# Tracking-Car.net
KiCad netlist of a schematic drawn in Altium Designer
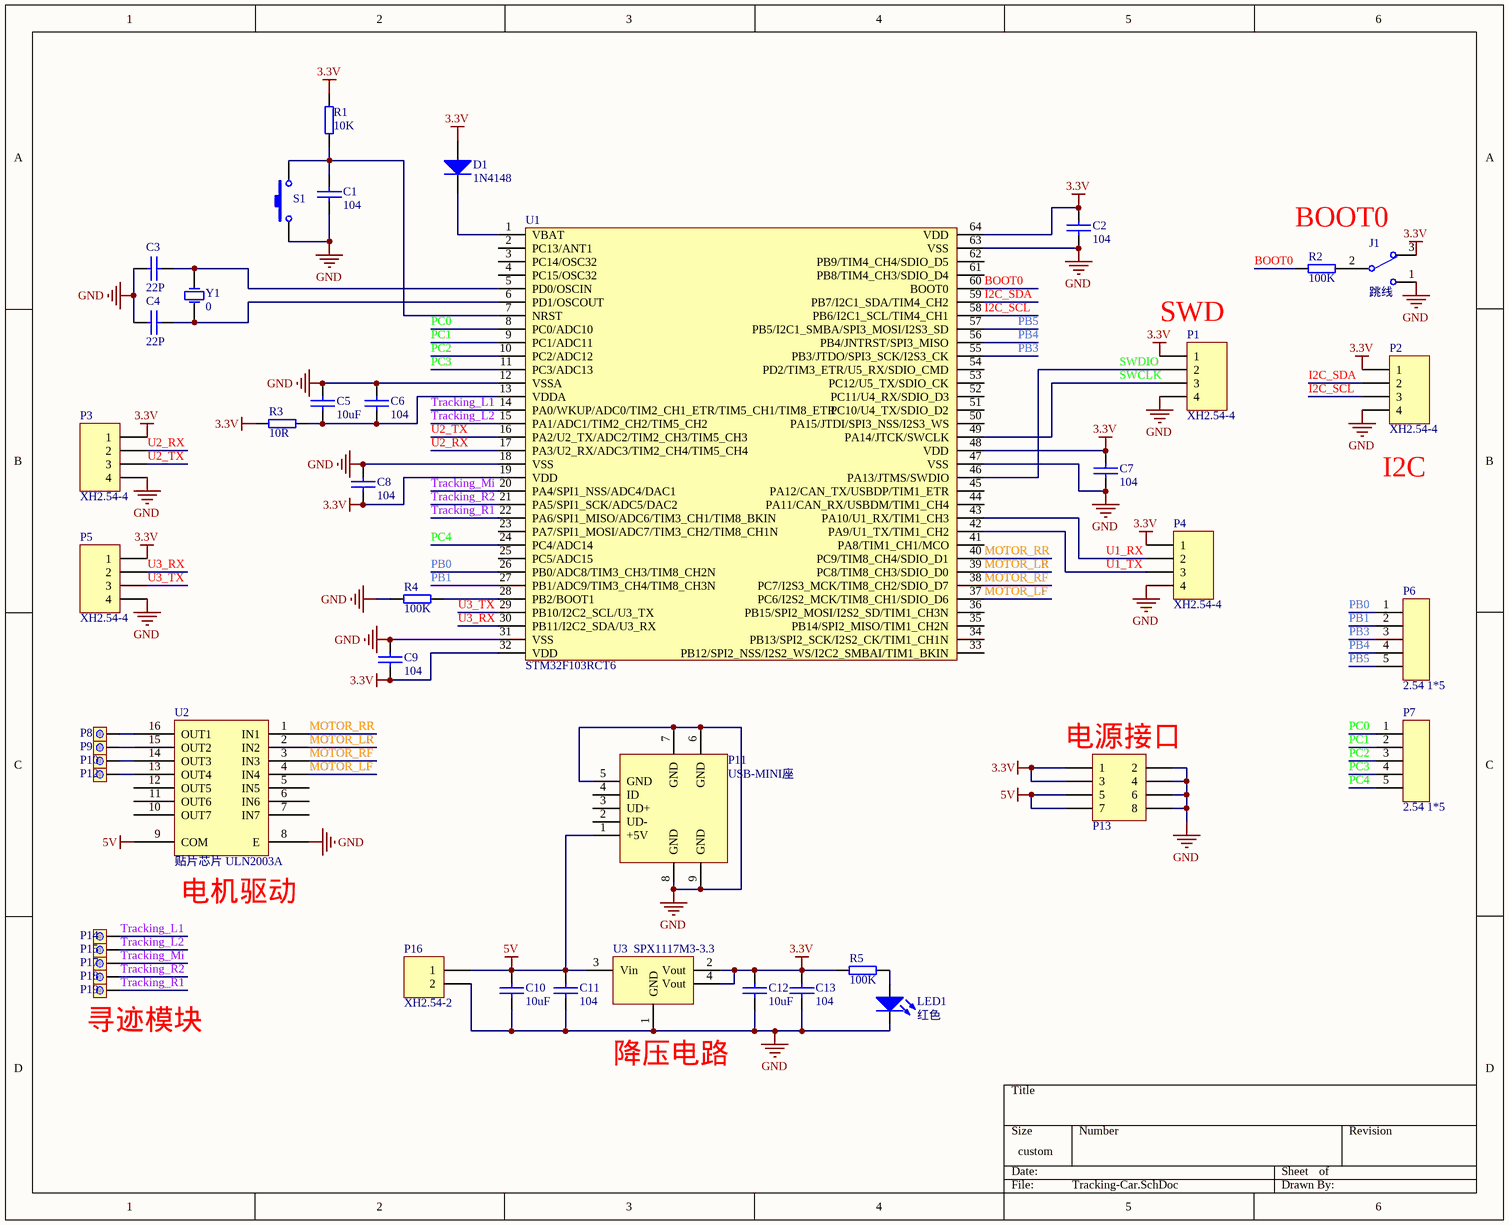
[diagram p0: Tracking-Car.SchDoc]

(export (version "E")
  (design (tool "Eeschema 10.0.6"))
  (components
    (comp (ref "C1")
      (value "104")
      (footprint "0805")
      (libsource (lib "Sch_Device_veryaz") (part "电容 贴片 0805"))
    )
    (comp (ref "C2")
      (value "104")
      (footprint "0805")
      (libsource (lib "Sch_Device_veryaz") (part "电容 贴片 0805"))
    )
    (comp (ref "C3")
      (value "22P")
      (footprint "0805")
      (libsource (lib "Sch_Device_veryaz") (part "电容 贴片 0805"))
    )
    (comp (ref "C4")
      (value "22P")
      (footprint "0805")
      (libsource (lib "Sch_Device_veryaz") (part "电容 贴片 0805"))
    )
    (comp (ref "C5")
      (value "10uF")
      (footprint "0805")
      (libsource (lib "Sch_Device_veryaz") (part "电容 贴片 0805"))
    )
    (comp (ref "C6")
      (value "104")
      (footprint "0805")
      (libsource (lib "Sch_Device_veryaz") (part "电容 贴片 0805"))
    )
    (comp (ref "C7")
      (value "104")
      (footprint "0805")
      (libsource (lib "Sch_Device_veryaz") (part "电容 贴片 0805"))
    )
    (comp (ref "C8")
      (value "104")
      (footprint "0805")
      (libsource (lib "Sch_Device_veryaz") (part "电容 贴片 0805"))
    )
    (comp (ref "C9")
      (value "104")
      (footprint "0805")
      (libsource (lib "Sch_Device_veryaz") (part "电容 贴片 0805"))
    )
    (comp (ref "C10")
      (value "10uF")
      (footprint "0805")
      (libsource (lib "Sch_Device_veryaz") (part "电容 贴片 0805"))
    )
    (comp (ref "C11")
      (value "104")
      (footprint "0805")
      (libsource (lib "Sch_Device_veryaz") (part "电容 贴片 0805"))
    )
    (comp (ref "C12")
      (value "10uF")
      (footprint "0805")
      (libsource (lib "Sch_Device_veryaz") (part "电容 贴片 0805"))
    )
    (comp (ref "C13")
      (value "104")
      (footprint "0805")
      (libsource (lib "Sch_Device_veryaz") (part "电容 贴片 0805"))
    )
    (comp (ref "D1")
      (value "1N4148")
      (footprint "二极管 贴片 IN4148")
      (libsource (lib "Sch_Device_veryaz") (part "二极管 贴片 1N4148"))
    )
    (comp (ref "J1")
      (value "跳线")
      (footprint "单排插针 2.54 1*3")
      (libsource (lib "Sch_Device_veryaz") (part "联结件 跳线端子 2.54-3"))
    )
    (comp (ref "LED1")
      (value "红色")
      (footprint "LED0805")
      (libsource (lib "Sch_Device_veryaz") (part "二极管 贴片发光 0805"))
    )
    (comp (ref "P1")
      (value "XH2.54-4")
      (footprint "VH2.54_4")
      (libsource (lib "Sch_Device_veryaz") (part "联结件 XH2.54-4"))
    )
    (comp (ref "P2")
      (value "XH2.54-4")
      (footprint "VH2.54_4")
      (libsource (lib "Sch_Device_veryaz") (part "联结件 XH2.54-4"))
    )
    (comp (ref "P3") (value "XH2.54-4") (footprint "VH2.54_4") (libsource (lib "") (part "联结件 XH2.54-4_1")))
    (comp (ref "P4")
      (value "XH2.54-4")
      (footprint "VH2.54_4")
      (libsource (lib "Sch_Device_veryaz") (part "联结件 XH2.54-4"))
    )
    (comp (ref "P5") (value "XH2.54-4") (footprint "VH2.54_4") (libsource (lib "") (part "联结件 XH2.54-4_1")))
    (comp (ref "P6")
      (value "2.54 1*5")
      (footprint "单排插针 2.54 1*5")
      (libsource (lib "Sch_Device_veryaz") (part "联结件 单排插针 2.54 1*5"))
    )
    (comp (ref "P7")
      (value "2.54 1*5")
      (footprint "单排插针 2.54 1*5")
      (libsource (lib "Sch_Device_veryaz") (part "联结件 单排插针 2.54 1*5"))
    )
    (comp (ref "P8") (value "TEST") (footprint "焊盘") (libsource (lib "Sch_Device_veryaz") (part "焊盘")))
    (comp (ref "P9") (value "TEST") (footprint "焊盘") (libsource (lib "Sch_Device_veryaz") (part "焊盘")))
    (comp (ref "P10") (value "TEST") (footprint "焊盘") (libsource (lib "Sch_Device_veryaz") (part "焊盘")))
    (comp (ref "P11")
      (value "USB-MINI座")
      (footprint "USB MINI DIP")
      (libsource (lib "Sch_Device_veryaz") (part "联结件 USB-MINI座"))
    )
    (comp (ref "P12") (value "TEST") (footprint "焊盘") (libsource (lib "Sch_Device_veryaz") (part "焊盘")))
    (comp (ref "P13")
      (value "双排插针 2.54 2*4")
      (footprint "双排插针 2.54 2*4")
      (libsource (lib "Sch_Device_veryaz") (part "联结件 双排插针 2.54 2*4"))
    )
    (comp (ref "P14") (value "TEST") (footprint "焊盘") (libsource (lib "Sch_Device_veryaz") (part "焊盘")))
    (comp (ref "P15") (value "TEST") (footprint "焊盘") (libsource (lib "Sch_Device_veryaz") (part "焊盘")))
    (comp (ref "P16")
      (value "XH2.54-2")
      (footprint "VH2.54_2")
      (libsource (lib "Sch_Device_veryaz") (part "联结件 XH2.54-2"))
    )
    (comp (ref "P17") (value "TEST") (footprint "焊盘") (libsource (lib "Sch_Device_veryaz") (part "焊盘")))
    (comp (ref "P18") (value "TEST") (footprint "焊盘") (libsource (lib "Sch_Device_veryaz") (part "焊盘")))
    (comp (ref "P19") (value "TEST") (footprint "焊盘") (libsource (lib "Sch_Device_veryaz") (part "焊盘")))
    (comp (ref "R1") (value "10K") (footprint "0805") (libsource (lib "") (part "电阻 贴片 0805_1")))
    (comp (ref "R2")
      (value "100K")
      (footprint "0805")
      (libsource (lib "Sch_Device_veryaz") (part "电阻 贴片 0805"))
    )
    (comp (ref "R3")
      (value "10R")
      (footprint "0805")
      (libsource (lib "Sch_Device_veryaz") (part "电阻 贴片 0805"))
    )
    (comp (ref "R4")
      (value "100K")
      (footprint "0805")
      (libsource (lib "Sch_Device_veryaz") (part "电阻 贴片 0805"))
    )
    (comp (ref "R5")
      (value "100K")
      (footprint "0805")
      (libsource (lib "Sch_Device_veryaz") (part "电阻 贴片 0805"))
    )
    (comp (ref "S1")
      (value "key")
      (footprint "按键 轻触  6*3")
      (libsource (lib "Sch_Device_veryaz") (part "按键 轻触 3*6"))
    )
    (comp (ref "U1")
      (value "STM32F103RCT6")
      (footprint "Pcb Device_veryaz:LQFP64")
      (description "单片机")
      (libsource (lib "Sch_Device_veryaz") (part "贴片芯片 STM32F103RCT6"))
    )
    (comp (ref "U2")
      (value "贴片芯片 ULN2003A")
      (footprint "SOIC16")
      (libsource (lib "Sch_Device_veryaz") (part "贴片芯片 ULN2003A"))
    )
    (comp (ref "U3")
      (value "SPX1117M3-3.3")
      (footprint "SOT223")
      (description "LDO")
      (libsource (lib "Sch_Device_veryaz") (part "贴片芯片 SPX1117M3-3.3"))
    )
    (comp (ref "Y1")
      (value "0")
      (footprint "晶振 BCY-W2/E4.7")
      (libsource (lib "Sch_Device_veryaz") (part "晶振 直插矮"))
    )
  )
  (nets
    (net (code "1") (name "/BOOT0") (class "Default")
      (node (ref "R2") (pin "2") (pinfunction "2_2") (pintype "passive"))
      (node (ref "U1") (pin "60") (pinfunction "BOOT0_60") (pintype "passive"))
    )
    (net (code "2") (name "/I2C_SCL") (class "Default")
      (node (ref "P2") (pin "3") (pinfunction "3_3") (pintype "passive"))
      (node (ref "U1") (pin "58") (pinfunction "PB6/I2C1_SCL/TIM4_CH1_58") (pintype "passive"))
    )
    (net (code "3") (name "/I2C_SDA") (class "Default")
      (node (ref "P2") (pin "2") (pinfunction "2_2") (pintype "passive"))
      (node (ref "U1") (pin "59") (pinfunction "PB7/I2C1_SDA/TIM4_CH2_59") (pintype "passive"))
    )
    (net (code "4") (name "/MOTOR_LF") (class "Default")
      (node (ref "U1") (pin "37") (pinfunction "PC6/I2S2_MCK/TIM8_CH1/SDIO_D6_37") (pintype "passive"))
      (node (ref "U2") (pin "4") (pinfunction "IN4_4") (pintype "passive"))
    )
    (net (code "5") (name "/MOTOR_LR") (class "Default")
      (node (ref "U1") (pin "39") (pinfunction "PC8/TIM8_CH3/SDIO_D0_39") (pintype "passive"))
      (node (ref "U2") (pin "2") (pinfunction "IN2_2") (pintype "passive"))
    )
    (net (code "6") (name "/MOTOR_RF") (class "Default")
      (node (ref "U1") (pin "38") (pinfunction "PC7/I2S3_MCK/TIM8_CH2/SDIO_D7_38") (pintype "passive"))
      (node (ref "U2") (pin "3") (pinfunction "IN3_3") (pintype "passive"))
    )
    (net (code "7") (name "/MOTOR_RR") (class "Default")
      (node (ref "U1") (pin "40") (pinfunction "PC9/TIM8_CH4/SDIO_D1_40") (pintype "passive"))
      (node (ref "U2") (pin "1") (pinfunction "IN1_1") (pintype "passive"))
    )
    (net (code "8") (name "/PB0") (class "Default")
      (node (ref "P6") (pin "1") (pinfunction "1_1") (pintype "passive"))
      (node (ref "U1") (pin "26") (pinfunction "PB0/ADC8/TIM3_CH3/TIM8_CH2N_26") (pintype "passive"))
    )
    (net (code "9") (name "/PB1") (class "Default")
      (node (ref "P6") (pin "2") (pinfunction "2_2") (pintype "passive"))
      (node (ref "U1") (pin "27") (pinfunction "PB1/ADC9/TIM3_CH4/TIM8_CH3N_27") (pintype "passive"))
    )
    (net (code "10") (name "/PB3") (class "Default")
      (node (ref "P6") (pin "3") (pinfunction "3_3") (pintype "passive"))
      (node (ref "U1") (pin "55") (pinfunction "PB3/JTDO/SPI3_SCK/I2S3_CK_55") (pintype "passive"))
    )
    (net (code "11") (name "/PB4") (class "Default")
      (node (ref "P6") (pin "4") (pinfunction "4_4") (pintype "passive"))
      (node (ref "U1") (pin "56") (pinfunction "PB4/JNTRST/SPI3_MISO_56") (pintype "passive"))
    )
    (net (code "12") (name "/PB5") (class "Default")
      (node (ref "P6") (pin "5") (pinfunction "5_5") (pintype "passive"))
      (node (ref "U1") (pin "57") (pinfunction "PB5/I2C1_SMBA/SPI3_MOSI/I2S3_SD_57") (pintype "passive"))
    )
    (net (code "13") (name "/PC0") (class "Default")
      (node (ref "P7") (pin "1") (pinfunction "1_1") (pintype "passive"))
      (node (ref "U1") (pin "8") (pinfunction "PC0/ADC10_8") (pintype "passive"))
    )
    (net (code "14") (name "/PC1") (class "Default")
      (node (ref "P7") (pin "2") (pinfunction "2_2") (pintype "passive"))
      (node (ref "U1") (pin "9") (pinfunction "PC1/ADC11_9") (pintype "passive"))
    )
    (net (code "15") (name "/PC2") (class "Default")
      (node (ref "P7") (pin "3") (pinfunction "3_3") (pintype "passive"))
      (node (ref "U1") (pin "10") (pinfunction "PC2/ADC12_10") (pintype "passive"))
    )
    (net (code "16") (name "/PC3") (class "Default")
      (node (ref "P7") (pin "4") (pinfunction "4_4") (pintype "passive"))
      (node (ref "U1") (pin "11") (pinfunction "PC3/ADC13_11") (pintype "passive"))
    )
    (net (code "17") (name "/PC4") (class "Default")
      (node (ref "P7") (pin "5") (pinfunction "5_5") (pintype "passive"))
      (node (ref "U1") (pin "24") (pinfunction "PC4/ADC14_24") (pintype "passive"))
    )
    (net (code "18") (name "/SWCLK") (class "Default")
      (node (ref "P1") (pin "3") (pinfunction "3_3") (pintype "passive"))
      (node (ref "U1") (pin "49") (pinfunction "PA14/JTCK/SWCLK_49") (pintype "passive"))
    )
    (net (code "19") (name "/SWDIO") (class "Default")
      (node (ref "P1") (pin "2") (pinfunction "2_2") (pintype "passive"))
      (node (ref "U1") (pin "46") (pinfunction "PA13/JTMS/SWDIO_46") (pintype "passive"))
    )
    (net (code "20") (name "/Tracking_L1") (class "Default")
      (node (ref "P14") (pin "1") (pinfunction "1_1") (pintype "passive"))
      (node (ref "U1") (pin "14") (pinfunction "PA0/WKUP/ADC0/TIM2_CH1_ETR/TIM5_CH1/TIM8_ETR_14") (pintype "passive"))
    )
    (net (code "21") (name "/Tracking_L2") (class "Default")
      (node (ref "P15") (pin "1") (pinfunction "1_1") (pintype "passive"))
      (node (ref "U1") (pin "15") (pinfunction "PA1/ADC1/TIM2_CH2/TIM5_CH2_15") (pintype "passive"))
    )
    (net (code "22") (name "/Tracking_Mi") (class "Default")
      (node (ref "P17") (pin "1") (pinfunction "1_1") (pintype "passive"))
      (node (ref "U1") (pin "20") (pinfunction "PA4/SPI1_NSS/ADC4/DAC1_20") (pintype "passive"))
    )
    (net (code "23") (name "/Tracking_R1") (class "Default")
      (node (ref "P19") (pin "1") (pinfunction "1_1") (pintype "passive"))
      (node (ref "U1") (pin "22") (pinfunction "PA6/SPI1_MISO/ADC6/TIM3_CH1/TIM8_BKIN_22") (pintype "passive"))
    )
    (net (code "24") (name "/Tracking_R2") (class "Default")
      (node (ref "P18") (pin "1") (pinfunction "1_1") (pintype "passive"))
      (node (ref "U1") (pin "21") (pinfunction "PA5/SPI1_SCK/ADC5/DAC2_21") (pintype "passive"))
    )
    (net (code "25") (name "/U1_RX") (class "Default")
      (node (ref "P4") (pin "2") (pinfunction "2_2") (pintype "passive"))
      (node (ref "U1") (pin "43") (pinfunction "PA10/U1_RX/TIM1_CH3_43") (pintype "passive"))
    )
    (net (code "26") (name "/U1_TX") (class "Default")
      (node (ref "P4") (pin "3") (pinfunction "3_3") (pintype "passive"))
      (node (ref "U1") (pin "42") (pinfunction "PA9/U1_TX/TIM1_CH2_42") (pintype "passive"))
    )
    (net (code "27") (name "/U2_RX") (class "Default")
      (node (ref "P3") (pin "2") (pinfunction "2_2") (pintype "passive"))
      (node (ref "U1") (pin "17") (pinfunction "PA3/U2_RX/ADC3/TIM2_CH4/TIM5_CH4_17") (pintype "passive"))
    )
    (net (code "28") (name "/U2_TX") (class "Default")
      (node (ref "P3") (pin "3") (pinfunction "3_3") (pintype "passive"))
      (node (ref "U1") (pin "16") (pinfunction "PA2/U2_TX/ADC2/TIM2_CH3/TIM5_CH3_16") (pintype "passive"))
    )
    (net (code "29") (name "/U3_RX") (class "Default")
      (node (ref "P5") (pin "2") (pinfunction "2_2") (pintype "passive"))
      (node (ref "U1") (pin "30") (pinfunction "PB11/I2C2_SDA/U3_RX_30") (pintype "passive"))
    )
    (net (code "30") (name "/U3_TX") (class "Default")
      (node (ref "P5") (pin "3") (pinfunction "3_3") (pintype "passive"))
      (node (ref "U1") (pin "29") (pinfunction "PB10/I2C2_SCL/U3_TX_29") (pintype "passive"))
    )
    (net (code "31") (name "3.3V") (class "Default")
      (node (ref "C12") (pin "2") (pintype "passive"))
      (node (ref "C13") (pin "2") (pintype "passive"))
      (node (ref "C2") (pin "2") (pintype "passive"))
      (node (ref "C7") (pin "1") (pintype "passive"))
      (node (ref "C8") (pin "1") (pintype "passive"))
      (node (ref "C9") (pin "1") (pintype "passive"))
      (node (ref "D1") (pin "1") (pinfunction "A_1") (pintype "passive"))
      (node (ref "J1") (pin "3") (pinfunction "3_3") (pintype "passive"))
      (node (ref "P1") (pin "1") (pinfunction "1_1") (pintype "passive"))
      (node (ref "P13") (pin "1") (pinfunction "1_1") (pintype "passive"))
      (node (ref "P13") (pin "3") (pinfunction "3_3") (pintype "passive"))
      (node (ref "P2") (pin "1") (pinfunction "1_1") (pintype "passive"))
      (node (ref "P3") (pin "1") (pinfunction "1_1") (pintype "passive"))
      (node (ref "P4") (pin "1") (pinfunction "1_1") (pintype "passive"))
      (node (ref "P5") (pin "1") (pinfunction "1_1") (pintype "passive"))
      (node (ref "R1") (pin "1") (pinfunction "1_1") (pintype "passive"))
      (node (ref "R3") (pin "2") (pinfunction "2_2") (pintype "passive"))
      (node (ref "R5") (pin "2") (pinfunction "2_2") (pintype "passive"))
      (node (ref "U1") (pin "19") (pinfunction "VDD_19") (pintype "passive"))
      (node (ref "U1") (pin "32") (pinfunction "VDD_32") (pintype "passive"))
      (node (ref "U1") (pin "48") (pinfunction "VDD_48") (pintype "passive"))
      (node (ref "U1") (pin "64") (pinfunction "VDD_64") (pintype "passive"))
      (node (ref "U3") (pin "2") (pinfunction "Vout_2") (pintype "passive"))
      (node (ref "U3") (pin "4") (pinfunction "Vout_4") (pintype "passive"))
    )
    (net (code "32") (name "5V") (class "Default")
      (node (ref "C10") (pin "2") (pintype "passive"))
      (node (ref "C11") (pin "2") (pintype "passive"))
      (node (ref "P11") (pin "1") (pinfunction "+5V_1") (pintype "passive"))
      (node (ref "P13") (pin "5") (pinfunction "5_5") (pintype "passive"))
      (node (ref "P13") (pin "7") (pinfunction "7_7") (pintype "passive"))
      (node (ref "P16") (pin "1") (pinfunction "1_1") (pintype "passive"))
      (node (ref "U2") (pin "9") (pinfunction "COM_9") (pintype "passive"))
      (node (ref "U3") (pin "3") (pinfunction "Vin_3") (pintype "passive"))
    )
    (net (code "33") (name "GND") (class "Default")
      (node (ref "C1") (pin "1") (pintype "passive"))
      (node (ref "C10") (pin "1") (pintype "passive"))
      (node (ref "C11") (pin "1") (pintype "passive"))
      (node (ref "C12") (pin "1") (pintype "passive"))
      (node (ref "C13") (pin "1") (pintype "passive"))
      (node (ref "C2") (pin "1") (pintype "passive"))
      (node (ref "C3") (pin "1") (pintype "passive"))
      (node (ref "C4") (pin "1") (pintype "passive"))
      (node (ref "C5") (pin "2") (pintype "passive"))
      (node (ref "C6") (pin "2") (pintype "passive"))
      (node (ref "C7") (pin "2") (pintype "passive"))
      (node (ref "C8") (pin "2") (pintype "passive"))
      (node (ref "C9") (pin "2") (pintype "passive"))
      (node (ref "J1") (pin "1") (pinfunction "1_1") (pintype "passive"))
      (node (ref "LED1") (pin "2") (pinfunction "K_2") (pintype "passive"))
      (node (ref "P1") (pin "4") (pinfunction "4_4") (pintype "passive"))
      (node (ref "P11") (pin "5") (pinfunction "GND_5") (pintype "passive"))
      (node (ref "P11") (pin "6") (pinfunction "GND_6") (pintype "passive"))
      (node (ref "P11") (pin "7") (pinfunction "GND_7") (pintype "passive"))
      (node (ref "P11") (pin "8") (pinfunction "GND_8") (pintype "passive"))
      (node (ref "P11") (pin "9") (pinfunction "GND_9") (pintype "passive"))
      (node (ref "P13") (pin "2") (pinfunction "2_2") (pintype "passive"))
      (node (ref "P13") (pin "4") (pinfunction "4_4") (pintype "passive"))
      (node (ref "P13") (pin "6") (pinfunction "6_6") (pintype "passive"))
      (node (ref "P13") (pin "8") (pinfunction "8_8") (pintype "passive"))
      (node (ref "P16") (pin "2") (pinfunction "2_2") (pintype "passive"))
      (node (ref "P2") (pin "4") (pinfunction "4_4") (pintype "passive"))
      (node (ref "P3") (pin "4") (pinfunction "4_4") (pintype "passive"))
      (node (ref "P4") (pin "4") (pinfunction "4_4") (pintype "passive"))
      (node (ref "P5") (pin "4") (pinfunction "4_4") (pintype "passive"))
      (node (ref "R4") (pin "2") (pinfunction "2_2") (pintype "passive"))
      (node (ref "S1") (pin "1") (pinfunction "1_1") (pintype "passive"))
      (node (ref "U1") (pin "12") (pinfunction "VSSA_12") (pintype "passive"))
      (node (ref "U1") (pin "18") (pinfunction "VSS_18") (pintype "passive"))
      (node (ref "U1") (pin "31") (pinfunction "VSS_31") (pintype "passive"))
      (node (ref "U1") (pin "47") (pinfunction "VSS_47") (pintype "passive"))
      (node (ref "U1") (pin "63") (pinfunction "VSS_63") (pintype "passive"))
      (node (ref "U2") (pin "8") (pinfunction "E_8") (pintype "passive"))
      (node (ref "U3") (pin "1") (pinfunction "GND_1") (pintype "passive"))
    )
    (net (code "34") (name "Net-(D1-K)") (class "Default")
      (node (ref "D1") (pin "2") (pinfunction "K_2") (pintype "passive"))
      (node (ref "U1") (pin "1") (pinfunction "VBAT_1") (pintype "passive"))
    )
    (net (code "35") (name "Net-(J1-Pad2)") (class "Default")
      (node (ref "J1") (pin "2") (pinfunction "2_2") (pintype "passive"))
      (node (ref "R2") (pin "1") (pinfunction "1_1") (pintype "passive"))
    )
    (net (code "36") (name "Net-(LED1-A)") (class "Default")
      (node (ref "LED1") (pin "1") (pinfunction "A_1") (pintype "passive"))
      (node (ref "R5") (pin "1") (pinfunction "1_1") (pintype "passive"))
    )
    (net (code "37") (name "Net-(U1-NRST)") (class "Default")
      (node (ref "C1") (pin "2") (pintype "passive"))
      (node (ref "R1") (pin "2") (pinfunction "2_2") (pintype "passive"))
      (node (ref "S1") (pin "2") (pinfunction "2_2") (pintype "passive"))
      (node (ref "U1") (pin "7") (pinfunction "NRST_7") (pintype "passive"))
    )
    (net (code "38") (name "Net-(U1-PB2{slash}BOOT1)") (class "Default")
      (node (ref "R4") (pin "1") (pinfunction "1_1") (pintype "passive"))
      (node (ref "U1") (pin "28") (pinfunction "PB2/BOOT1_28") (pintype "passive"))
    )
    (net (code "39") (name "Net-(U1-PD0{slash}OSCIN)") (class "Default")
      (node (ref "C3") (pin "2") (pintype "passive"))
      (node (ref "U1") (pin "5") (pinfunction "PD0/OSCIN_5") (pintype "passive"))
      (node (ref "Y1") (pin "2") (pinfunction "OSC2_2") (pintype "passive"))
    )
    (net (code "40") (name "Net-(U1-PD1{slash}OSCOUT)") (class "Default")
      (node (ref "C4") (pin "2") (pintype "passive"))
      (node (ref "U1") (pin "6") (pinfunction "PD1/OSCOUT_6") (pintype "passive"))
      (node (ref "Y1") (pin "1") (pinfunction "OSC1_1") (pintype "passive"))
    )
    (net (code "41") (name "Net-(U1-VDDA)") (class "Default")
      (node (ref "C5") (pin "1") (pintype "passive"))
      (node (ref "C6") (pin "1") (pintype "passive"))
      (node (ref "R3") (pin "1") (pinfunction "1_1") (pintype "passive"))
      (node (ref "U1") (pin "13") (pinfunction "VDDA_13") (pintype "passive"))
    )
    (net (code "42") (name "Net-(U2-OUT1)") (class "Default")
      (node (ref "P8") (pin "1") (pinfunction "1_1") (pintype "passive"))
      (node (ref "U2") (pin "16") (pinfunction "OUT1_16") (pintype "passive"))
    )
    (net (code "43") (name "Net-(U2-OUT2)") (class "Default")
      (node (ref "P9") (pin "1") (pinfunction "1_1") (pintype "passive"))
      (node (ref "U2") (pin "15") (pinfunction "OUT2_15") (pintype "passive"))
    )
    (net (code "44") (name "Net-(U2-OUT3)") (class "Default")
      (node (ref "P10") (pin "1") (pinfunction "1_1") (pintype "passive"))
      (node (ref "U2") (pin "14") (pinfunction "OUT3_14") (pintype "passive"))
    )
    (net (code "45") (name "Net-(U2-OUT4)") (class "Default")
      (node (ref "P12") (pin "1") (pinfunction "1_1") (pintype "passive"))
      (node (ref "U2") (pin "13") (pinfunction "OUT4_13") (pintype "passive"))
    )
    (net (code "46") (name "unconnected-(P11-ID-Pad4)") (class "Default")
      (node (ref "P11") (pin "4") (pinfunction "ID_4") (pintype "passive"))
    )
    (net (code "47") (name "unconnected-(P11-UD+-Pad3)") (class "Default")
      (node (ref "P11") (pin "3") (pinfunction "UD+_3") (pintype "passive"))
    )
    (net (code "48") (name "unconnected-(P11-UD--Pad2)") (class "Default")
      (node (ref "P11") (pin "2") (pinfunction "UD-_2") (pintype "passive"))
    )
    (net (code "49") (name "unconnected-(U1-PA7{slash}SPI1_MOSI{slash}ADC7{slash}TIM3_CH2{slash}TIM8_CH1N-Pad23)") (class "Default")
      (node (ref "U1") (pin "23") (pinfunction "PA7/SPI1_MOSI/ADC7/TIM3_CH2/TIM8_CH1N_23") (pintype "passive"))
    )
    (net (code "50") (name "unconnected-(U1-PA8{slash}TIM1_CH1{slash}MCO-Pad41)") (class "Default")
      (node (ref "U1") (pin "41") (pinfunction "PA8/TIM1_CH1/MCO_41") (pintype "passive"))
    )
    (net (code "51") (name "unconnected-(U1-PA11{slash}CAN_RX{slash}USBDM{slash}TIM1_CH4-Pad44)") (class "Default")
      (node (ref "U1") (pin "44") (pinfunction "PA11/CAN_RX/USBDM/TIM1_CH4_44") (pintype "passive"))
    )
    (net (code "52") (name "unconnected-(U1-PA12{slash}CAN_TX{slash}USBDP{slash}TIM1_ETR-Pad45)") (class "Default")
      (node (ref "U1") (pin "45") (pinfunction "PA12/CAN_TX/USBDP/TIM1_ETR_45") (pintype "passive"))
    )
    (net (code "53") (name "unconnected-(U1-PA15{slash}JTDI{slash}SPI3_NSS{slash}I2S3_WS-Pad50)") (class "Default")
      (node (ref "U1") (pin "50") (pinfunction "PA15/JTDI/SPI3_NSS/I2S3_WS_50") (pintype "passive"))
    )
    (net (code "54") (name "unconnected-(U1-PB8{slash}TIM4_CH3{slash}SDIO_D4-Pad61)") (class "Default")
      (node (ref "U1") (pin "61") (pinfunction "PB8/TIM4_CH3/SDIO_D4_61") (pintype "passive"))
    )
    (net (code "55") (name "unconnected-(U1-PB9{slash}TIM4_CH4{slash}SDIO_D5-Pad62)") (class "Default")
      (node (ref "U1") (pin "62") (pinfunction "PB9/TIM4_CH4/SDIO_D5_62") (pintype "passive"))
    )
    (net (code "56") (name "unconnected-(U1-PB12{slash}SPI2_NSS{slash}I2S2_WS{slash}I2C2_SMBAI{slash}TIM1_BKIN-Pad33)") (class "Default")
      (node (ref "U1") (pin "33") (pinfunction "PB12/SPI2_NSS/I2S2_WS/I2C2_SMBAI/TIM1_BKIN_33") (pintype "passive"))
    )
    (net (code "57") (name "unconnected-(U1-PB13{slash}SPI2_SCK{slash}I2S2_CK{slash}TIM1_CH1N-Pad34)") (class "Default")
      (node (ref "U1") (pin "34") (pinfunction "PB13/SPI2_SCK/I2S2_CK/TIM1_CH1N_34") (pintype "passive"))
    )
    (net (code "58") (name "unconnected-(U1-PB14{slash}SPI2_MISO{slash}TIM1_CH2N-Pad35)") (class "Default")
      (node (ref "U1") (pin "35") (pinfunction "PB14/SPI2_MISO/TIM1_CH2N_35") (pintype "passive"))
    )
    (net (code "59") (name "unconnected-(U1-PB15{slash}SPI2_MOSI{slash}I2S2_SD{slash}TIM1_CH3N-Pad36)") (class "Default")
      (node (ref "U1") (pin "36") (pinfunction "PB15/SPI2_MOSI/I2S2_SD/TIM1_CH3N_36") (pintype "passive"))
    )
    (net (code "60") (name "unconnected-(U1-PC5{slash}ADC15-Pad25)") (class "Default")
      (node (ref "U1") (pin "25") (pinfunction "PC5/ADC15_25") (pintype "passive"))
    )
    (net (code "61") (name "unconnected-(U1-PC10{slash}U4_TX{slash}SDIO_D2-Pad51)") (class "Default")
      (node (ref "U1") (pin "51") (pinfunction "PC10/U4_TX/SDIO_D2_51") (pintype "passive"))
    )
    (net (code "62") (name "unconnected-(U1-PC11{slash}U4_RX{slash}SDIO_D3-Pad52)") (class "Default")
      (node (ref "U1") (pin "52") (pinfunction "PC11/U4_RX/SDIO_D3_52") (pintype "passive"))
    )
    (net (code "63") (name "unconnected-(U1-PC12{slash}U5_TX{slash}SDIO_CK-Pad53)") (class "Default")
      (node (ref "U1") (pin "53") (pinfunction "PC12/U5_TX/SDIO_CK_53") (pintype "passive"))
    )
    (net (code "64") (name "unconnected-(U1-PC13{slash}ANT1-Pad2)") (class "Default")
      (node (ref "U1") (pin "2") (pinfunction "PC13/ANT1_2") (pintype "passive"))
    )
    (net (code "65") (name "unconnected-(U1-PC14{slash}OSC32-Pad3)") (class "Default")
      (node (ref "U1") (pin "3") (pinfunction "PC14/OSC32_3") (pintype "passive"))
    )
    (net (code "66") (name "unconnected-(U1-PC15{slash}OSC32-Pad4)") (class "Default")
      (node (ref "U1") (pin "4") (pinfunction "PC15/OSC32_4") (pintype "passive"))
    )
    (net (code "67") (name "unconnected-(U1-PD2{slash}TIM3_ETR{slash}U5_RX{slash}SDIO_CMD-Pad54)") (class "Default")
      (node (ref "U1") (pin "54") (pinfunction "PD2/TIM3_ETR/U5_RX/SDIO_CMD_54") (pintype "passive"))
    )
    (net (code "68") (name "unconnected-(U2-IN5-Pad5)") (class "Default")
      (node (ref "U2") (pin "5") (pinfunction "IN5_5") (pintype "passive"))
    )
    (net (code "69") (name "unconnected-(U2-IN6-Pad6)") (class "Default")
      (node (ref "U2") (pin "6") (pinfunction "IN6_6") (pintype "passive"))
    )
    (net (code "70") (name "unconnected-(U2-IN7-Pad7)") (class "Default")
      (node (ref "U2") (pin "7") (pinfunction "IN7_7") (pintype "passive"))
    )
    (net (code "71") (name "unconnected-(U2-OUT5-Pad12)") (class "Default")
      (node (ref "U2") (pin "12") (pinfunction "OUT5_12") (pintype "passive"))
    )
    (net (code "72") (name "unconnected-(U2-OUT6-Pad11)") (class "Default")
      (node (ref "U2") (pin "11") (pinfunction "OUT6_11") (pintype "passive"))
    )
    (net (code "73") (name "unconnected-(U2-OUT7-Pad10)") (class "Default")
      (node (ref "U2") (pin "10") (pinfunction "OUT7_10") (pintype "passive"))
    )
  )
)
